# Thermistor.net
KiCad netlist of a schematic drawn in Altium Designer
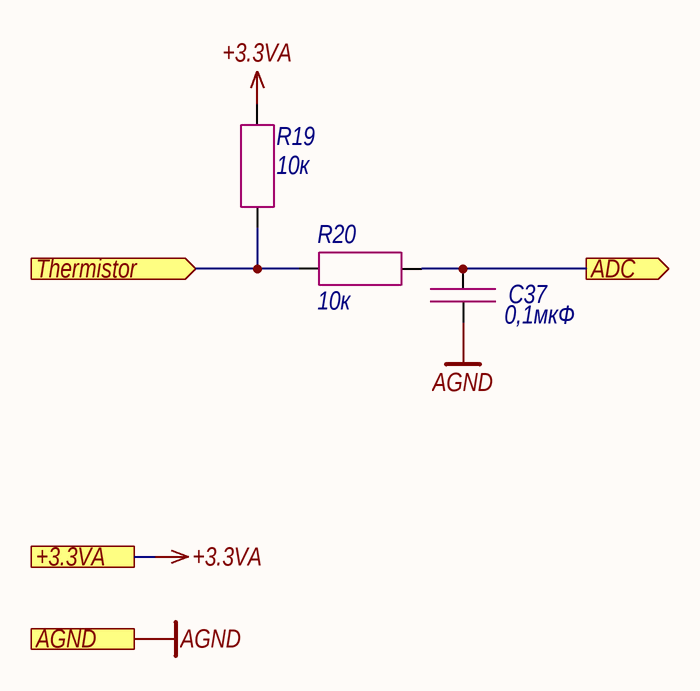
[diagram p0: Thermistor.SchDoc]

(export (version "E")
  (design (tool "Eeschema 10.0.6"))
  (components
    (comp (ref "C37")
      (value "0,1мкФ")
      (footprint "Pcb_library:CAP_0603")
      (fields (field (name "MANUFACTURER") "Murata"))
      (libsource (lib "Schem_library") (part "Capacitor"))
    )
    (comp (ref "R19")
      (value "10к")
      (footprint "Pcb_library:RES_0603")
      (fields (field (name "MANUFACTURER") "Yageo"))
      (libsource (lib "Schem_library") (part "Resistor"))
    )
    (comp (ref "R20")
      (value "10к")
      (footprint "Pcb_library:RES_0603")
      (fields (field (name "MANUFACTURER") "Yageo"))
      (libsource (lib "Schem_library") (part "Resistor"))
    )
  )
  (nets
    (net (code "1") (name "+3.3VA") (class "Default")
      (node (ref "R19") (pin "1") (pinfunction "1_1") (pintype "passive"))
    )
    (net (code "2") (name "/ADC") (class "Default")
      (node (ref "C37") (pin "1") (pinfunction "1_1") (pintype "passive"))
      (node (ref "R20") (pin "2") (pinfunction "2_2") (pintype "passive"))
    )
    (net (code "3") (name "/Thermistor") (class "Default")
      (node (ref "R19") (pin "2") (pinfunction "2_2") (pintype "passive"))
      (node (ref "R20") (pin "1") (pinfunction "1_1") (pintype "passive"))
    )
    (net (code "4") (name "AGND") (class "Default")
      (node (ref "C37") (pin "2") (pinfunction "2_2") (pintype "passive"))
    )
  )
)
